# vanity_lights-v1.net
KiCad netlist of a schematic drawn in EAGLE
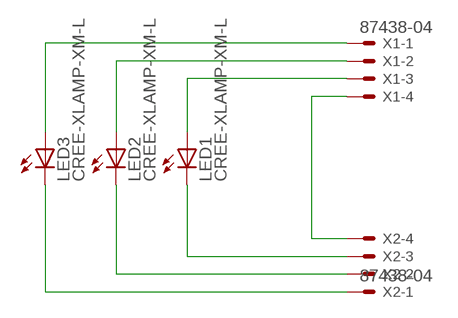
[diagram p0: schematic, sheet 1]

(export (version "E")
  (design (tool "Eeschema 10.0.6"))
  (components
    (comp (ref "LED1")
      (value "CREE-XLAMP-XM-L")
      (footprint "eagle-import:CREE-XLAMP-XM-L")
      (libsource (lib "eagle-import") (part "CREE-XLAMP-XM-L"))
    )
    (comp (ref "LED2")
      (value "CREE-XLAMP-XM-L")
      (footprint "eagle-import:CREE-XLAMP-XM-L")
      (libsource (lib "eagle-import") (part "CREE-XLAMP-XM-L"))
    )
    (comp (ref "LED3")
      (value "CREE-XLAMP-XM-L")
      (footprint "eagle-import:CREE-XLAMP-XM-L")
      (libsource (lib "eagle-import") (part "CREE-XLAMP-XM-L"))
    )
    (comp (ref "X1")
      (value "87438-04")
      (footprint "eagle-import:87438-04")
      (libsource (lib "eagle-import") (part "87438-04"))
    )
    (comp (ref "X2")
      (value "87438-04")
      (footprint "eagle-import:87438-04")
      (libsource (lib "eagle-import") (part "87438-04"))
    )
  )
  (nets
    (net (code "1") (name "Net-(X1A-S)") (class "Default")
      (node (ref "LED3") (pin "A") (pinfunction "A_A") (pintype "passive"))
      (node (ref "LED3") (pin "A@1") (pinfunction "A_A@1") (pintype "passive"))
      (node (ref "X1") (pin "1") (pinfunction "S_1") (pintype "passive"))
    )
    (net (code "2") (name "Net-(X1B-S)") (class "Default")
      (node (ref "LED2") (pin "A") (pinfunction "A_A") (pintype "passive"))
      (node (ref "LED2") (pin "A@1") (pinfunction "A_A@1") (pintype "passive"))
      (node (ref "X1") (pin "2") (pinfunction "S_2") (pintype "passive"))
    )
    (net (code "3") (name "Net-(X1C-S)") (class "Default")
      (node (ref "LED1") (pin "A") (pinfunction "A_A") (pintype "passive"))
      (node (ref "LED1") (pin "A@1") (pinfunction "A_A@1") (pintype "passive"))
      (node (ref "X1") (pin "3") (pinfunction "S_3") (pintype "passive"))
    )
    (net (code "4") (name "Net-(X1D-S)") (class "Default")
      (node (ref "X1") (pin "4") (pinfunction "S_4") (pintype "passive"))
      (node (ref "X2") (pin "4") (pinfunction "S_4") (pintype "passive"))
    )
    (net (code "5") (name "Net-(X2A-S)") (class "Default")
      (node (ref "LED3") (pin "C") (pinfunction "C_C") (pintype "passive"))
      (node (ref "LED3") (pin "C@1") (pinfunction "C_C@1") (pintype "passive"))
      (node (ref "X2") (pin "1") (pinfunction "S_1") (pintype "passive"))
    )
    (net (code "6") (name "Net-(X2B-S)") (class "Default")
      (node (ref "LED2") (pin "C") (pinfunction "C_C") (pintype "passive"))
      (node (ref "LED2") (pin "C@1") (pinfunction "C_C@1") (pintype "passive"))
      (node (ref "X2") (pin "2") (pinfunction "S_2") (pintype "passive"))
    )
    (net (code "7") (name "Net-(X2C-S)") (class "Default")
      (node (ref "LED1") (pin "C") (pinfunction "C_C") (pintype "passive"))
      (node (ref "LED1") (pin "C@1") (pinfunction "C_C@1") (pintype "passive"))
      (node (ref "X2") (pin "3") (pinfunction "S_3") (pintype "passive"))
    )
  )
)
